# SCH_card0_2025-06-05.net
KiCad netlist of a schematic drawn in EasyEDA
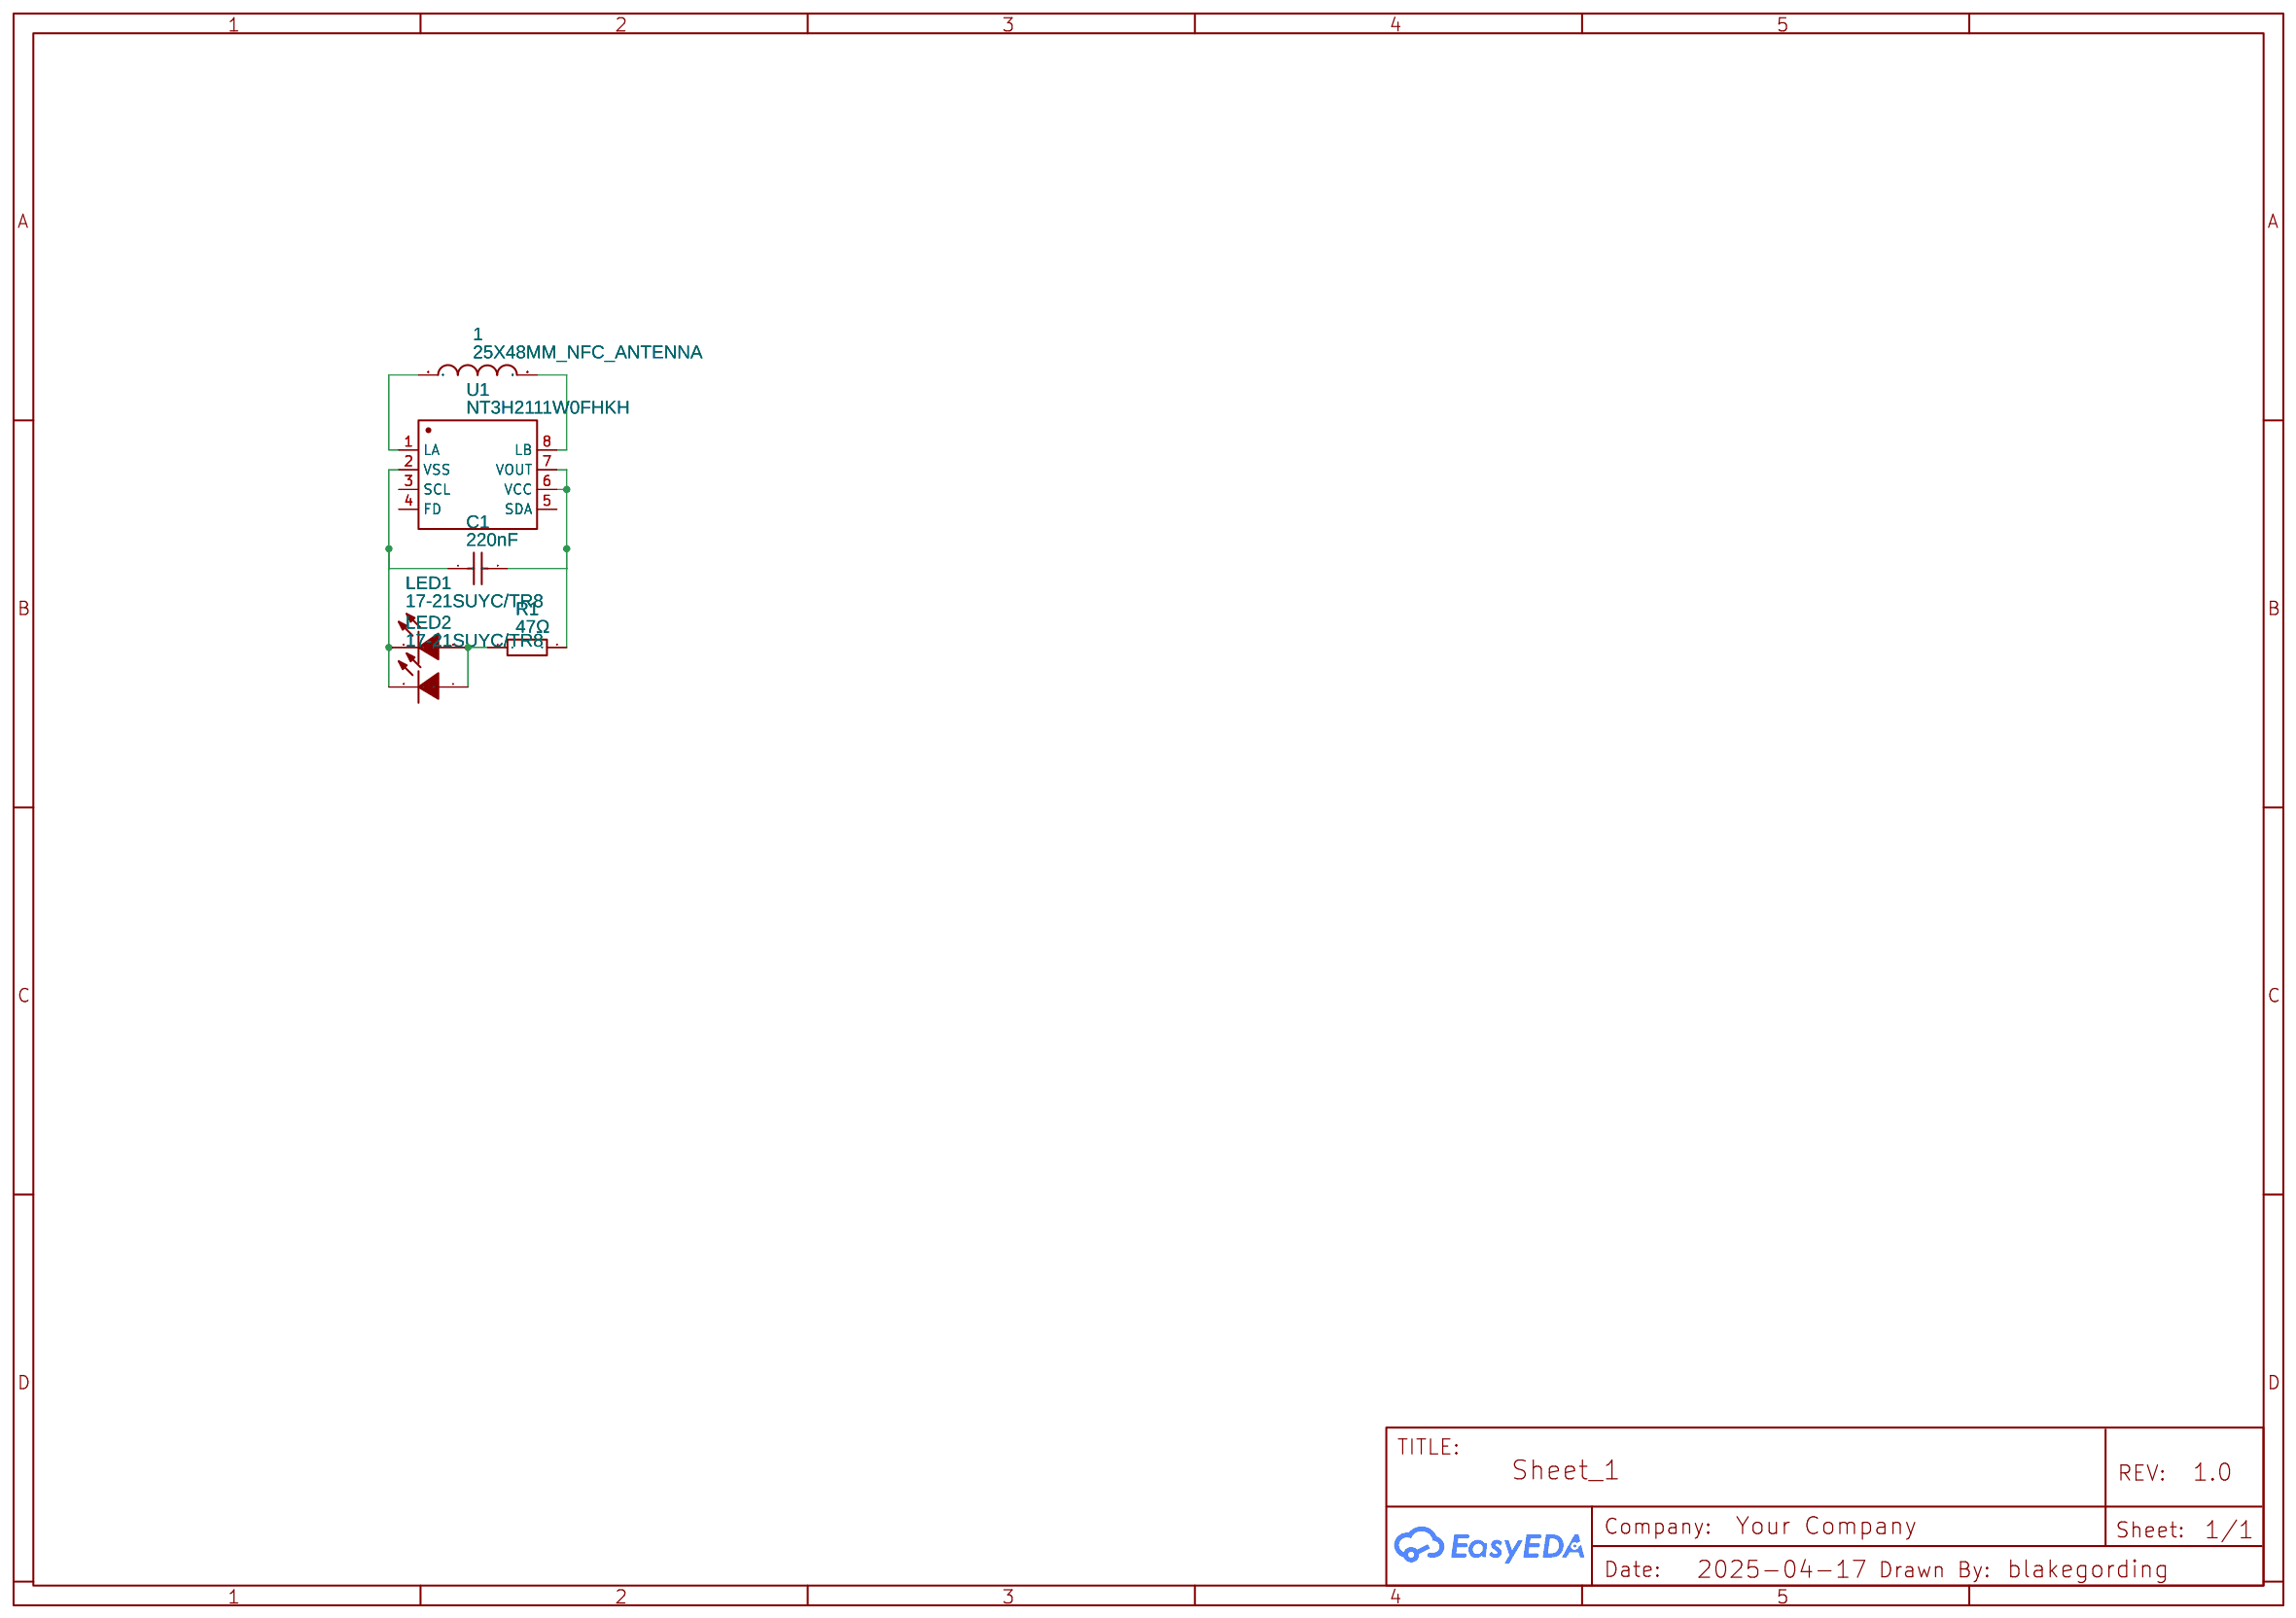
[diagram p0: schematic sheet]

(export (version "E")
  (design (tool "Eeschema 10.0.6"))
  (components
    (comp (ref "1") (value "25X48MM_NFC_ANTENNA") (libsource (lib "") (part "25X48MM_NFC_ANTENNA")))
    (comp (ref "C1")
      (value "220nF")
      (fields
        (field (name "Manufacturer Part") "CL10B224KA8NNNC")
        (field (name "Manufacturer") "SAMSUNG(三星)")
      )
      (libsource (lib "") (part "CL10B224KA8NNNC"))
    )
    (comp (ref "LED1")
      (value "17-21SUYC/TR8")
      (fields (field (name "Manufacturer Part") "KT-0805黄灯") (field (name "Manufacturer") "KENTO"))
      (libsource (lib "") (part "17-21SUYC/TR8"))
    )
    (comp (ref "LED2")
      (value "17-21SUYC/TR8")
      (fields (field (name "Manufacturer Part") "KT-0805黄灯") (field (name "Manufacturer") "KENTO"))
      (libsource (lib "") (part "17-21SUYC/TR8"))
    )
    (comp (ref "R1")
      (value "47Ω")
      (fields
        (field (name "Manufacturer Part") "0603WAF470JT5E")
        (field (name "Manufacturer") "UNI-ROYAL(厚声)")
      )
      (libsource (lib "") (part "0603WAF470JT5E"))
    )
    (comp (ref "U1")
      (value "NT3H2111W0FHKH")
      (fields (field (name "Manufacturer") "NXP(恩智浦)"))
      (libsource (lib "") (part "NT3H2111W0FHKH"))
    )
  )
  (nets
    (net (code "1") (name "Net-(LED1-+)") (class "Default")
      (node (ref "LED1") (pin "1") (pinfunction "+_1") (pintype "unspecified"))
      (node (ref "LED2") (pin "1") (pinfunction "+_1") (pintype "unspecified"))
      (node (ref "R1") (pin "1") (pinfunction "1_1") (pintype "input"))
    )
    (net (code "2") (name "Net-(LED1--)") (class "Default")
      (node (ref "C1") (pin "1") (pinfunction "1_1") (pintype "input"))
      (node (ref "LED1") (pin "2") (pinfunction "-_2") (pintype "unspecified"))
      (node (ref "LED2") (pin "2") (pinfunction "-_2") (pintype "unspecified"))
      (node (ref "U1") (pin "2") (pinfunction "VSS_2") (pintype "unspecified"))
    )
    (net (code "3") (name "Net-(U1-LA)") (class "Default")
      (node (ref "1") (pin "P$1") (pinfunction "P$1_P$1") (pintype "bidirectional"))
      (node (ref "U1") (pin "1") (pinfunction "LA_1") (pintype "unspecified"))
    )
    (net (code "4") (name "Net-(U1-LB)") (class "Default")
      (node (ref "1") (pin "P$2") (pinfunction "P$2_P$2") (pintype "bidirectional"))
      (node (ref "U1") (pin "8") (pinfunction "LB_8") (pintype "unspecified"))
    )
    (net (code "5") (name "Net-(U1-VCC)") (class "Default")
      (node (ref "C1") (pin "2") (pinfunction "2_2") (pintype "input"))
      (node (ref "R1") (pin "2") (pinfunction "2_2") (pintype "input"))
      (node (ref "U1") (pin "6") (pinfunction "VCC_6") (pintype "unspecified"))
      (node (ref "U1") (pin "7") (pinfunction "VOUT_7") (pintype "unspecified"))
    )
    (net (code "6") (name "unconnected-(U1-FD-Pad4)") (class "Default")
      (node (ref "U1") (pin "4") (pinfunction "FD_4") (pintype "unspecified"))
    )
    (net (code "7") (name "unconnected-(U1-SCL-Pad3)") (class "Default")
      (node (ref "U1") (pin "3") (pinfunction "SCL_3") (pintype "unspecified"))
    )
    (net (code "8") (name "unconnected-(U1-SDA-Pad5)") (class "Default")
      (node (ref "U1") (pin "5") (pinfunction "SDA_5") (pintype "unspecified"))
    )
  )
)
